# openbook.net
KiCad netlist of a schematic drawn in EAGLE
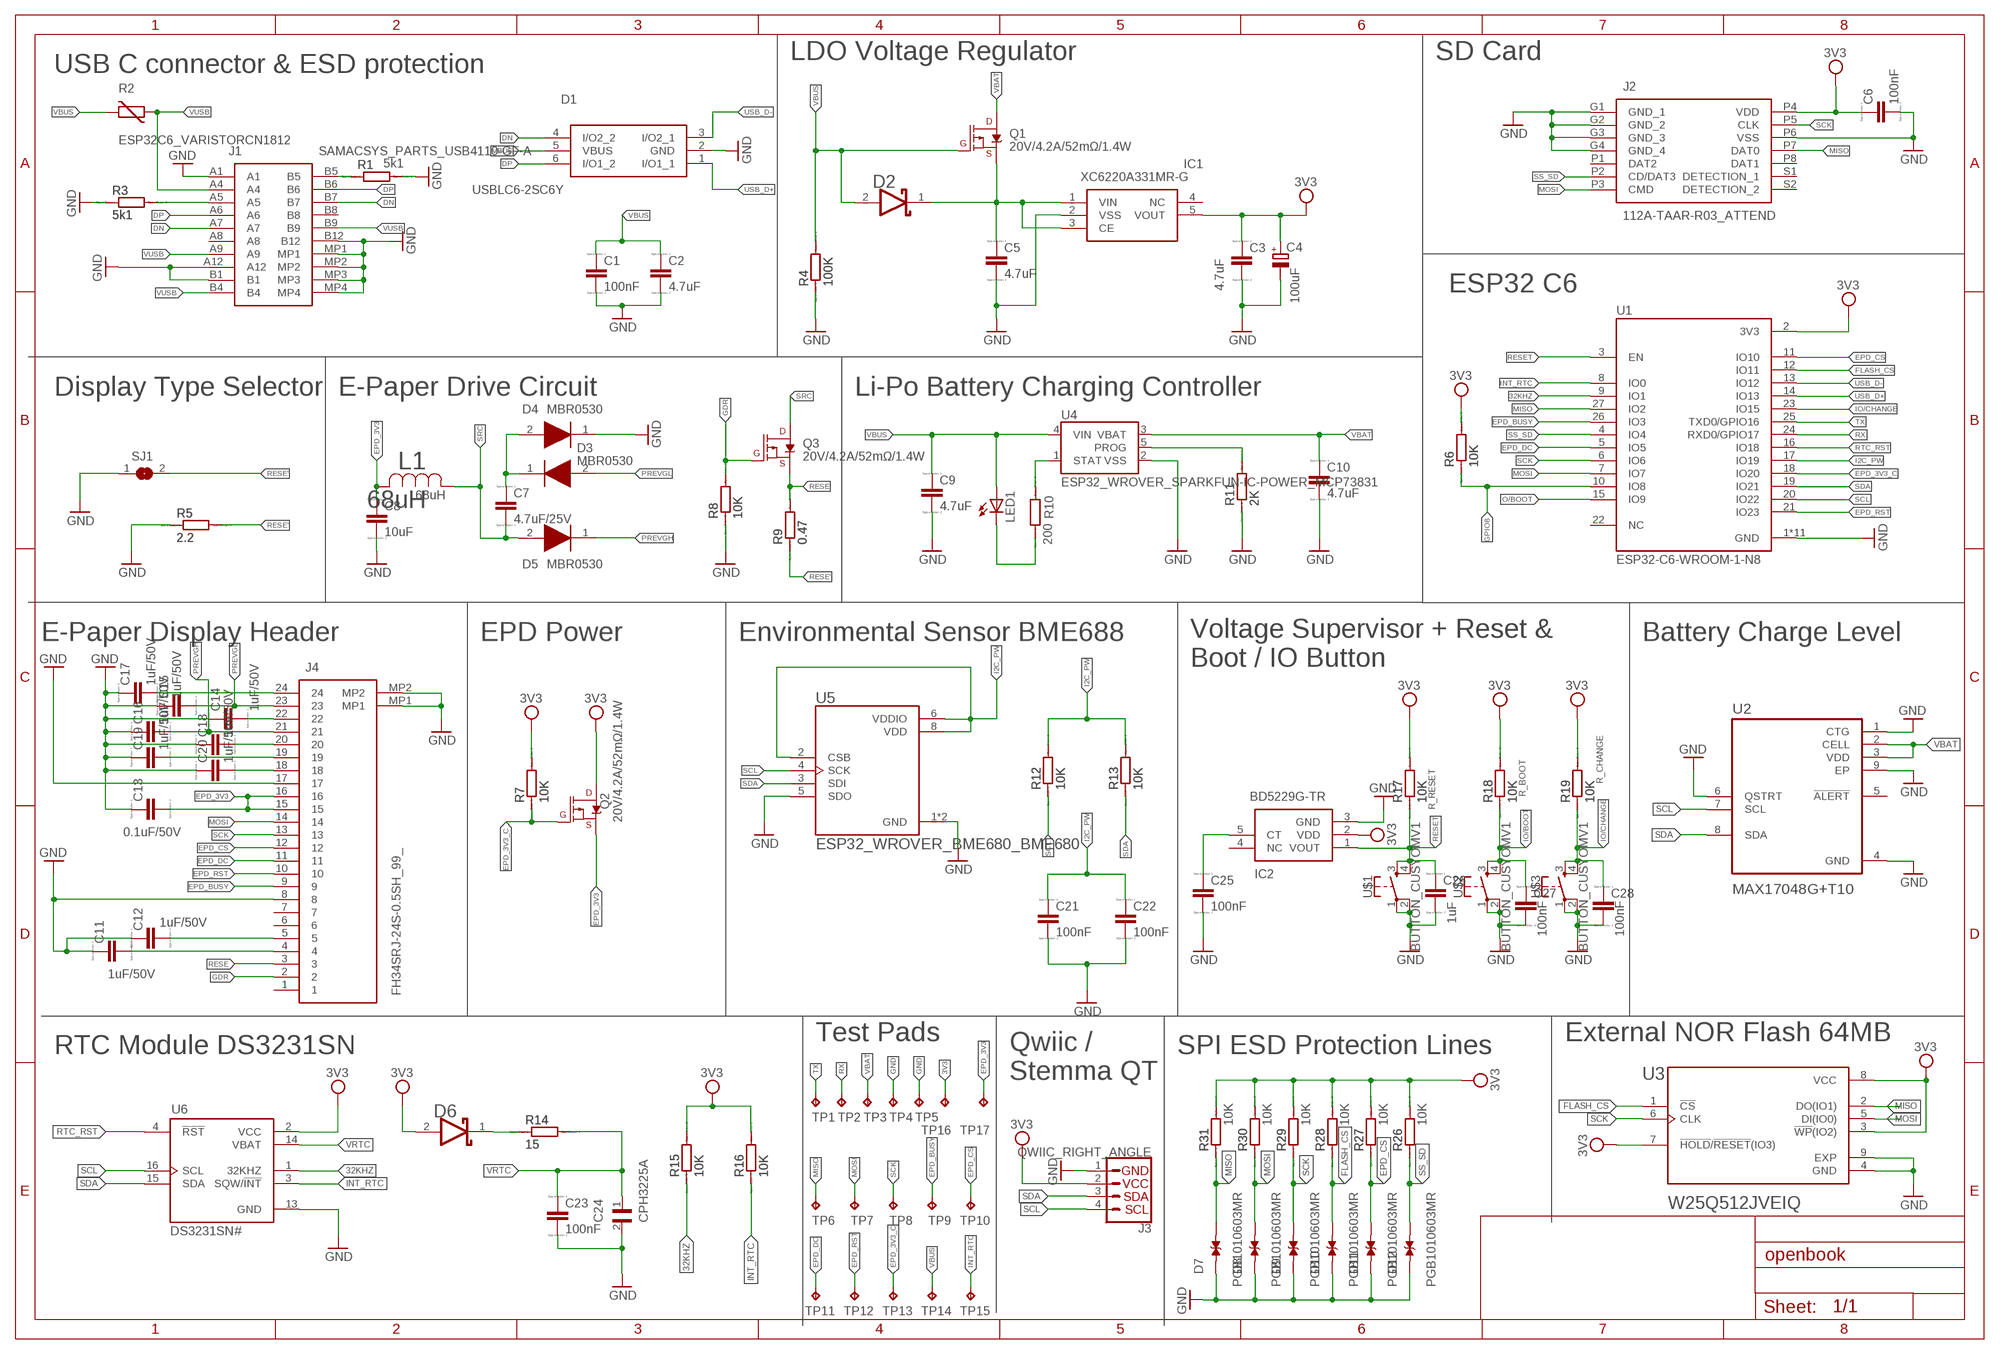
[diagram p0: schematic, sheet 1]

(export (version "E")
  (design (tool "Eeschema 10.0.6"))
  (components
    (comp (ref "C1")
      (value "100nF")
      (footprint "eagle-import:EAGLE-LTSPICE_C0402")
      (libsource (lib "eagle-import") (part "EAGLE-LTSPICE_CC0402"))
    )
    (comp (ref "C2")
      (value "4.7uF")
      (footprint "eagle-import:EAGLE-LTSPICE_C0402")
      (libsource (lib "eagle-import") (part "EAGLE-LTSPICE_CC0402"))
    )
    (comp (ref "C3")
      (value "4.7uF")
      (footprint "eagle-import:EAGLE-LTSPICE_C0402")
      (libsource (lib "eagle-import") (part "EAGLE-LTSPICE_CC0402"))
    )
    (comp (ref "C4")
      (value "100uF")
      (footprint "eagle-import:RCL_CT3528")
      (libsource (lib "eagle-import") (part "RCL_CPOL-EUCT3528"))
    )
    (comp (ref "C5")
      (value "4.7uF")
      (footprint "eagle-import:EAGLE-LTSPICE_C0402")
      (libsource (lib "eagle-import") (part "EAGLE-LTSPICE_CC0402"))
    )
    (comp (ref "C6")
      (value "100nF")
      (footprint "eagle-import:EAGLE-LTSPICE_C0402")
      (libsource (lib "eagle-import") (part "EAGLE-LTSPICE_CC0402"))
    )
    (comp (ref "C7")
      (value "4.7uF/25V")
      (footprint "eagle-import:EAGLE-LTSPICE_C0402")
      (libsource (lib "eagle-import") (part "EAGLE-LTSPICE_CC0402"))
    )
    (comp (ref "C8")
      (value "10uF")
      (footprint "eagle-import:EAGLE-LTSPICE_C0402")
      (libsource (lib "eagle-import") (part "EAGLE-LTSPICE_CC0402"))
    )
    (comp (ref "C9")
      (value "4.7uF")
      (footprint "eagle-import:EAGLE-LTSPICE_C0402")
      (libsource (lib "eagle-import") (part "EAGLE-LTSPICE_CC0402"))
    )
    (comp (ref "C10")
      (value "4.7uF")
      (footprint "eagle-import:EAGLE-LTSPICE_C0402")
      (libsource (lib "eagle-import") (part "EAGLE-LTSPICE_CC0402"))
    )
    (comp (ref "C11")
      (value "1uF/50V")
      (footprint "eagle-import:EAGLE-LTSPICE_C0402")
      (libsource (lib "eagle-import") (part "EAGLE-LTSPICE_CC0402"))
    )
    (comp (ref "C12")
      (value "1uF/50V")
      (footprint "eagle-import:EAGLE-LTSPICE_C0402")
      (libsource (lib "eagle-import") (part "EAGLE-LTSPICE_CC0402"))
    )
    (comp (ref "C13")
      (value "0.1uF/50V")
      (footprint "eagle-import:EAGLE-LTSPICE_C0402")
      (libsource (lib "eagle-import") (part "EAGLE-LTSPICE_CC0402"))
    )
    (comp (ref "C14")
      (value "1uF/50V")
      (footprint "eagle-import:EAGLE-LTSPICE_C0402")
      (libsource (lib "eagle-import") (part "EAGLE-LTSPICE_CC0402"))
    )
    (comp (ref "C15")
      (value "1uF/50V")
      (footprint "eagle-import:EAGLE-LTSPICE_C0402")
      (libsource (lib "eagle-import") (part "EAGLE-LTSPICE_CC0402"))
    )
    (comp (ref "C16")
      (value "1uF/50V")
      (footprint "eagle-import:EAGLE-LTSPICE_C0402")
      (libsource (lib "eagle-import") (part "EAGLE-LTSPICE_CC0402"))
    )
    (comp (ref "C17")
      (value "1uF/50V")
      (footprint "eagle-import:EAGLE-LTSPICE_C0402")
      (libsource (lib "eagle-import") (part "EAGLE-LTSPICE_CC0402"))
    )
    (comp (ref "C18")
      (value "1uF/50V")
      (footprint "eagle-import:EAGLE-LTSPICE_C0402")
      (libsource (lib "eagle-import") (part "EAGLE-LTSPICE_CC0402"))
    )
    (comp (ref "C19")
      (value "1uF/50V")
      (footprint "eagle-import:EAGLE-LTSPICE_C0402")
      (libsource (lib "eagle-import") (part "EAGLE-LTSPICE_CC0402"))
    )
    (comp (ref "C20")
      (value "1uF/50V")
      (footprint "eagle-import:EAGLE-LTSPICE_C0402")
      (libsource (lib "eagle-import") (part "EAGLE-LTSPICE_CC0402"))
    )
    (comp (ref "C21")
      (value "100nF")
      (footprint "eagle-import:EAGLE-LTSPICE_C0402")
      (libsource (lib "eagle-import") (part "EAGLE-LTSPICE_CC0402"))
    )
    (comp (ref "C22")
      (value "100nF")
      (footprint "eagle-import:EAGLE-LTSPICE_C0402")
      (libsource (lib "eagle-import") (part "EAGLE-LTSPICE_CC0402"))
    )
    (comp (ref "C23")
      (value "100nF")
      (footprint "eagle-import:EAGLE-LTSPICE_C0402")
      (libsource (lib "eagle-import") (part "EAGLE-LTSPICE_CC0402"))
    )
    (comp (ref "C24")
      (value "CPH3225A")
      (footprint "eagle-import:CAPCP3225X100N")
      (fields (field (name "MF") "Seiko Instruments"))
      (libsource (lib "eagle-import") (part "CPH3225A"))
    )
    (comp (ref "C25")
      (value "100nF")
      (footprint "eagle-import:EAGLE-LTSPICE_C0402")
      (libsource (lib "eagle-import") (part "EAGLE-LTSPICE_CC0402"))
    )
    (comp (ref "C26")
      (value "1uF")
      (footprint "eagle-import:EAGLE-LTSPICE_C0402")
      (libsource (lib "eagle-import") (part "EAGLE-LTSPICE_CC0402"))
    )
    (comp (ref "C27")
      (value "100nF")
      (footprint "eagle-import:EAGLE-LTSPICE_C0402")
      (libsource (lib "eagle-import") (part "EAGLE-LTSPICE_CC0402"))
    )
    (comp (ref "C28")
      (value "100nF")
      (footprint "eagle-import:EAGLE-LTSPICE_C0402")
      (libsource (lib "eagle-import") (part "EAGLE-LTSPICE_CC0402"))
    )
    (comp (ref "D1")
      (value "USBLC6-2SC6Y")
      (footprint "eagle-import:SOT95P280X145-6N")
      (fields (field (name "MF") "STMicroelectronics"))
      (libsource (lib "eagle-import") (part "USBLC6-2SC6Y"))
    )
    (comp (ref "D2")
      (value "ESP32_WROVER_AVX---SD0805S020S1R0_AVX_SD0805S020S1R0_0_0AVX_SD0805S020S1R0_0_0")
      (footprint "eagle-import:ESP32_WROVER_AVX---SD0805S020S1R0_AVX_SD0805S020S1R0_0")
      (fields
        (field (name "DIGIKEY_PART_NUMBER") "478-7800-1-ND")
        (field (name "MF") "AVX")
        (field (name "MOUSER_PART_NUMBER") "581-SD0805S020S1R0")
      )
      (libsource (lib "eagle-import") (part "ESP32_WROVER_AVX---SD0805S020S1R0_AVX_SD0805S020S1R0_0_0AVX_SD0805S020S1R0_0_0"))
    )
    (comp (ref "D3")
      (value "MBR0530")
      (footprint "eagle-import:SOD3716X135N")
      (fields (field (name "MF") "ON Semiconductor"))
      (libsource (lib "eagle-import") (part "MBR0530"))
    )
    (comp (ref "D4")
      (value "MBR0530")
      (footprint "eagle-import:SOD3716X135N")
      (fields (field (name "MF") "ON Semiconductor"))
      (libsource (lib "eagle-import") (part "MBR0530"))
    )
    (comp (ref "D5")
      (value "MBR0530")
      (footprint "eagle-import:SOD3716X135N")
      (fields (field (name "MF") "ON Semiconductor"))
      (libsource (lib "eagle-import") (part "MBR0530"))
    )
    (comp (ref "D6")
      (value "ESP32_WROVER_AVX---SD0805S020S1R0_AVX_SD0805S020S1R0_0_0AVX_SD0805S020S1R0_0_0")
      (footprint "eagle-import:ESP32_WROVER_AVX---SD0805S020S1R0_AVX_SD0805S020S1R0_0")
      (fields
        (field (name "DIGIKEY_PART_NUMBER") "478-7800-1-ND")
        (field (name "MF") "AVX")
        (field (name "MOUSER_PART_NUMBER") "581-SD0805S020S1R0")
      )
      (libsource (lib "eagle-import") (part "ESP32_WROVER_AVX---SD0805S020S1R0_AVX_SD0805S020S1R0_0_0AVX_SD0805S020S1R0_0_0"))
    )
    (comp (ref "D7")
      (value "PGB1010603MR")
      (footprint "eagle-import:DIOC1608X36N")
      (fields (field (name "MF") "Littelfuse Inc."))
      (libsource (lib "eagle-import") (part "PGB1010603MR"))
    )
    (comp (ref "D8")
      (value "PGB1010603MR")
      (footprint "eagle-import:DIOC1608X36N")
      (fields (field (name "MF") "Littelfuse Inc."))
      (libsource (lib "eagle-import") (part "PGB1010603MR"))
    )
    (comp (ref "D9")
      (value "PGB1010603MR")
      (footprint "eagle-import:DIOC1608X36N")
      (fields (field (name "MF") "Littelfuse Inc."))
      (libsource (lib "eagle-import") (part "PGB1010603MR"))
    )
    (comp (ref "D10")
      (value "PGB1010603MR")
      (footprint "eagle-import:DIOC1608X36N")
      (fields (field (name "MF") "Littelfuse Inc."))
      (libsource (lib "eagle-import") (part "PGB1010603MR"))
    )
    (comp (ref "D11")
      (value "PGB1010603MR")
      (footprint "eagle-import:DIOC1608X36N")
      (fields (field (name "MF") "Littelfuse Inc."))
      (libsource (lib "eagle-import") (part "PGB1010603MR"))
    )
    (comp (ref "D12")
      (value "PGB1010603MR")
      (footprint "eagle-import:DIOC1608X36N")
      (fields (field (name "MF") "Littelfuse Inc."))
      (libsource (lib "eagle-import") (part "PGB1010603MR"))
    )
    (comp (ref "IC1")
      (value "XC6220A331MR-G")
      (footprint "eagle-import:SOT95P280X120-5N")
      (fields (field (name "MOUSER_PART_NUMBER") "865-XC6220A331MR-G"))
      (libsource (lib "eagle-import") (part "XC6220A331MR-G"))
    )
    (comp (ref "IC2")
      (value "BD5229G-TR")
      (footprint "eagle-import:SOT95P280X125-5N")
      (fields (field (name "MOUSER_PART_NUMBER") "755-BD5229G-TR"))
      (libsource (lib "eagle-import") (part "BD5229G-TR"))
    )
    (comp (ref "J1")
      (value "SAMACSYS_PARTS_USB4110-GF-A")
      (footprint "eagle-import:SAMACSYS_PARTS_USB4110GFA")
      (fields
        (field (name "MANUFACTURER_PART_NUMBER") "USB4110-GF-A")
        (field (name "MOUSER_PART_NUMBER") "640-USB4110-GF-A")
      )
      (libsource (lib "eagle-import") (part "SAMACSYS_PARTS_USB4110-GF-A"))
    )
    (comp (ref "J2")
      (value "112A-TAAR-R03_ATTEND")
      (footprint "eagle-import:112ATAARR03ATTEND")
      (fields (field (name "MANUFACTURER_PART_NUMBER") "112A-TAAR-R03 ATTEND"))
      (libsource (lib "eagle-import") (part "112A-TAAR-R03_ATTEND"))
    )
    (comp (ref "J3")
      (value "QWIIC_RIGHT_ANGLE")
      (footprint "eagle-import:JST04_1MM_RA")
      (libsource (lib "eagle-import") (part "QWIIC_CONNECTORJS-1MM"))
    )
    (comp (ref "J4")
      (value "FH34SRJ-24S-0.5SH_99_")
      (footprint "eagle-import:FH34SRJ24S05SH99")
      (fields
        (field (name "MANUFACTURER_PART_NUMBER") "FH34SRJ-24S-0.5SH(99)")
        (field (name "MOUSER_PART_NUMBER") "798-FH34SRJ24S05SH99")
      )
      (libsource (lib "eagle-import") (part "FH34SRJ-24S-0.5SH_99_"))
    )
    (comp (ref "L1")
      (value "68uH")
      (footprint "eagle-import:IND_4828-WE-TPC_WRE")
      (fields
        (field (name "MANUFACTURER_PART_NUMBER") "744043680")
        (field (name "COPYRIGHT") "Copyright (C) 2024 Ultra Librarian. All rights reserved.")
      )
      (libsource (lib "eagle-import") (part "744043680IND_4828-WE-TPC_WRE"))
    )
    (comp (ref "LED1")
      (value "ADAFRUIT_LEDCHIP-LED0603")
      (footprint "eagle-import:ADAFRUIT_CHIP-LED0603")
      (libsource (lib "eagle-import") (part "ADAFRUIT_LEDCHIP-LED0603"))
    )
    (comp (ref "Q1")
      (value "20V/4.2A/52mΩ/1.4W")
      (footprint "eagle-import:ESP32_WROVER_SPARKFUN-DISCRETESEMI_SOT23-3")
      (libsource (lib "eagle-import") (part "ESP32_WROVER_SPARKFUN-DISCRETESEMI_MOSFET_PCH-DMG2305UX-7"))
    )
    (comp (ref "Q2")
      (value "20V/4.2A/52mΩ/1.4W")
      (footprint "eagle-import:ESP32_WROVER_SPARKFUN-DISCRETESEMI_SOT23-3")
      (libsource (lib "eagle-import") (part "ESP32_WROVER_SPARKFUN-DISCRETESEMI_MOSFET_PCH-DMG2305UX-7"))
    )
    (comp (ref "Q3")
      (value "20V/4.2A/52mΩ/1.4W")
      (footprint "eagle-import:ESP32_WROVER_SPARKFUN-DISCRETESEMI_SOT23-3")
      (libsource (lib "eagle-import") (part "ESP32_WROVER_SPARKFUN-DISCRETESEMI_MOSFET_PCH-DMG2305UX-7"))
    )
    (comp (ref "R1")
      (value "5k1")
      (footprint "eagle-import:ESP32_WROVER_EAGLE-LTSPICE_R0402")
      (libsource (lib "eagle-import") (part "ESP32_WROVER_EAGLE-LTSPICE_RR0402"))
    )
    (comp (ref "R2")
      (value "ESP32C6_VARISTORCN1812")
      (footprint "eagle-import:ESP32C6_VARISTOR_CT_CN1812")
      (libsource (lib "eagle-import") (part "ESP32C6_VARISTORCN1812"))
    )
    (comp (ref "R3")
      (value "5k1")
      (footprint "eagle-import:ESP32_WROVER_EAGLE-LTSPICE_R0402")
      (libsource (lib "eagle-import") (part "ESP32_WROVER_EAGLE-LTSPICE_RR0402"))
    )
    (comp (ref "R4")
      (value "100K")
      (footprint "eagle-import:ESP32_WROVER_EAGLE-LTSPICE_R0402")
      (libsource (lib "eagle-import") (part "ESP32_WROVER_EAGLE-LTSPICE_RR0402"))
    )
    (comp (ref "R5")
      (value "2.2")
      (footprint "eagle-import:ESP32_WROVER_EAGLE-LTSPICE_R0402")
      (libsource (lib "eagle-import") (part "ESP32_WROVER_EAGLE-LTSPICE_RR0402"))
    )
    (comp (ref "R6")
      (value "10K")
      (footprint "eagle-import:ESP32_WROVER_EAGLE-LTSPICE_R0402")
      (libsource (lib "eagle-import") (part "ESP32_WROVER_EAGLE-LTSPICE_RR0402"))
    )
    (comp (ref "R7")
      (value "10K")
      (footprint "eagle-import:ESP32_WROVER_EAGLE-LTSPICE_R0402")
      (libsource (lib "eagle-import") (part "ESP32_WROVER_EAGLE-LTSPICE_RR0402"))
    )
    (comp (ref "R8")
      (value "10K")
      (footprint "eagle-import:ESP32_WROVER_EAGLE-LTSPICE_R0402")
      (libsource (lib "eagle-import") (part "ESP32_WROVER_EAGLE-LTSPICE_RR0402"))
    )
    (comp (ref "R9")
      (value "0.47")
      (footprint "eagle-import:ESP32_WROVER_EAGLE-LTSPICE_R0402")
      (libsource (lib "eagle-import") (part "ESP32_WROVER_EAGLE-LTSPICE_RR0402"))
    )
    (comp (ref "R10")
      (value "200")
      (footprint "eagle-import:ESP32_WROVER_EAGLE-LTSPICE_R0402")
      (libsource (lib "eagle-import") (part "ESP32_WROVER_EAGLE-LTSPICE_RR0402"))
    )
    (comp (ref "R11")
      (value "2K")
      (footprint "eagle-import:ESP32_WROVER_EAGLE-LTSPICE_R0402")
      (libsource (lib "eagle-import") (part "ESP32_WROVER_EAGLE-LTSPICE_RR0402"))
    )
    (comp (ref "R12")
      (value "10K")
      (footprint "eagle-import:ESP32_WROVER_EAGLE-LTSPICE_R0402")
      (libsource (lib "eagle-import") (part "ESP32_WROVER_EAGLE-LTSPICE_RR0402"))
    )
    (comp (ref "R13")
      (value "10K")
      (footprint "eagle-import:ESP32_WROVER_EAGLE-LTSPICE_R0402")
      (libsource (lib "eagle-import") (part "ESP32_WROVER_EAGLE-LTSPICE_RR0402"))
    )
    (comp (ref "R14")
      (value "15")
      (footprint "eagle-import:ESP32_WROVER_EAGLE-LTSPICE_R0402")
      (libsource (lib "eagle-import") (part "ESP32_WROVER_EAGLE-LTSPICE_RR0402"))
    )
    (comp (ref "R15")
      (value "10K")
      (footprint "eagle-import:ESP32_WROVER_EAGLE-LTSPICE_R0402")
      (libsource (lib "eagle-import") (part "ESP32_WROVER_EAGLE-LTSPICE_RR0402"))
    )
    (comp (ref "R16")
      (value "10K")
      (footprint "eagle-import:ESP32_WROVER_EAGLE-LTSPICE_R0402")
      (libsource (lib "eagle-import") (part "ESP32_WROVER_EAGLE-LTSPICE_RR0402"))
    )
    (comp (ref "R17")
      (value "10K")
      (footprint "eagle-import:ESP32_WROVER_EAGLE-LTSPICE_R0402")
      (libsource (lib "eagle-import") (part "ESP32_WROVER_EAGLE-LTSPICE_RR0402"))
    )
    (comp (ref "R18")
      (value "10K")
      (footprint "eagle-import:ESP32_WROVER_EAGLE-LTSPICE_R0402")
      (libsource (lib "eagle-import") (part "ESP32_WROVER_EAGLE-LTSPICE_RR0402"))
    )
    (comp (ref "R19")
      (value "10K")
      (footprint "eagle-import:ESP32_WROVER_EAGLE-LTSPICE_R0402")
      (libsource (lib "eagle-import") (part "ESP32_WROVER_EAGLE-LTSPICE_RR0402"))
    )
    (comp (ref "R26")
      (value "10K")
      (footprint "eagle-import:ESP32_WROVER_EAGLE-LTSPICE_R0402")
      (libsource (lib "eagle-import") (part "ESP32_WROVER_EAGLE-LTSPICE_RR0402"))
    )
    (comp (ref "R27")
      (value "10K")
      (footprint "eagle-import:ESP32_WROVER_EAGLE-LTSPICE_R0402")
      (libsource (lib "eagle-import") (part "ESP32_WROVER_EAGLE-LTSPICE_RR0402"))
    )
    (comp (ref "R28")
      (value "10K")
      (footprint "eagle-import:ESP32_WROVER_EAGLE-LTSPICE_R0402")
      (libsource (lib "eagle-import") (part "ESP32_WROVER_EAGLE-LTSPICE_RR0402"))
    )
    (comp (ref "R29")
      (value "10K")
      (footprint "eagle-import:ESP32_WROVER_EAGLE-LTSPICE_R0402")
      (libsource (lib "eagle-import") (part "ESP32_WROVER_EAGLE-LTSPICE_RR0402"))
    )
    (comp (ref "R30")
      (value "10K")
      (footprint "eagle-import:ESP32_WROVER_EAGLE-LTSPICE_R0402")
      (libsource (lib "eagle-import") (part "ESP32_WROVER_EAGLE-LTSPICE_RR0402"))
    )
    (comp (ref "R31")
      (value "10K")
      (footprint "eagle-import:ESP32_WROVER_EAGLE-LTSPICE_R0402")
      (libsource (lib "eagle-import") (part "ESP32_WROVER_EAGLE-LTSPICE_RR0402"))
    )
    (comp (ref "SJ1") (value "SJ") (footprint "eagle-import:SJ") (libsource (lib "eagle-import") (part "SJ")))
    (comp (ref "TP1")
      (value "TPTP20R")
      (footprint "eagle-import:TP20R")
      (libsource (lib "eagle-import") (part "TPTP20R"))
    )
    (comp (ref "TP2")
      (value "TPTP20R")
      (footprint "eagle-import:TP20R")
      (libsource (lib "eagle-import") (part "TPTP20R"))
    )
    (comp (ref "TP3")
      (value "TPTP20R")
      (footprint "eagle-import:TP20R")
      (libsource (lib "eagle-import") (part "TPTP20R"))
    )
    (comp (ref "TP4")
      (value "TPTP20R")
      (footprint "eagle-import:TP20R")
      (libsource (lib "eagle-import") (part "TPTP20R"))
    )
    (comp (ref "TP5")
      (value "TPTP20R")
      (footprint "eagle-import:TP20R")
      (libsource (lib "eagle-import") (part "TPTP20R"))
    )
    (comp (ref "TP6")
      (value "TPTP20R")
      (footprint "eagle-import:TP20R")
      (libsource (lib "eagle-import") (part "TPTP20R"))
    )
    (comp (ref "TP7")
      (value "TPTP20R")
      (footprint "eagle-import:TP20R")
      (libsource (lib "eagle-import") (part "TPTP20R"))
    )
    (comp (ref "TP8")
      (value "TPTP20R")
      (footprint "eagle-import:TP20R")
      (libsource (lib "eagle-import") (part "TPTP20R"))
    )
    (comp (ref "TP9")
      (value "TPTP20R")
      (footprint "eagle-import:TP20R")
      (libsource (lib "eagle-import") (part "TPTP20R"))
    )
    (comp (ref "TP10")
      (value "TPTP20R")
      (footprint "eagle-import:TP20R")
      (libsource (lib "eagle-import") (part "TPTP20R"))
    )
    (comp (ref "TP11")
      (value "TPTP20R")
      (footprint "eagle-import:TP20R")
      (libsource (lib "eagle-import") (part "TPTP20R"))
    )
    (comp (ref "TP12")
      (value "TPTP20R")
      (footprint "eagle-import:TP20R")
      (libsource (lib "eagle-import") (part "TPTP20R"))
    )
    (comp (ref "TP13")
      (value "TPTP20R")
      (footprint "eagle-import:TP20R")
      (libsource (lib "eagle-import") (part "TPTP20R"))
    )
    (comp (ref "TP14")
      (value "TPTP20R")
      (footprint "eagle-import:TP20R")
      (libsource (lib "eagle-import") (part "TPTP20R"))
    )
    (comp (ref "TP15")
      (value "TPTP20R")
      (footprint "eagle-import:TP20R")
      (libsource (lib "eagle-import") (part "TPTP20R"))
    )
    (comp (ref "TP16")
      (value "TPTP20R")
      (footprint "eagle-import:TP20R")
      (libsource (lib "eagle-import") (part "TPTP20R"))
    )
    (comp (ref "TP17")
      (value "TPTP20R")
      (footprint "eagle-import:TP20R")
      (libsource (lib "eagle-import") (part "TPTP20R"))
    )
    (comp (ref "U$1")
      (value "BUTTON_CUSYOMV1")
      (footprint "eagle-import:MYBUTTON")
      (libsource (lib "eagle-import") (part "BUTTON_CUSYOMV1"))
    )
    (comp (ref "U$2")
      (value "BUTTON_CUSYOMV1")
      (footprint "eagle-import:MYBUTTON")
      (libsource (lib "eagle-import") (part "BUTTON_CUSYOMV1"))
    )
    (comp (ref "U$3")
      (value "BUTTON_CUSYOMV1")
      (footprint "eagle-import:MYBUTTON")
      (libsource (lib "eagle-import") (part "BUTTON_CUSYOMV1"))
    )
    (comp (ref "U1")
      (value "ESP32-C6-WROOM-1-N8")
      (footprint "eagle-import:XCVR_ESP32-C6-WROOM-1-N8")
      (fields (field (name "MF") "Espressif Systems"))
      (libsource (lib "eagle-import") (part "ESP32-C6-WROOM-1-N8"))
    )
    (comp (ref "U2")
      (value "MAX17048G+T10")
      (footprint "eagle-import:SON50P200X200X80-9N")
      (fields (field (name "MF") "Analog Devices"))
      (libsource (lib "eagle-import") (part "MAX17048G+T10"))
    )
    (comp (ref "U3")
      (value "W25Q512JVEIQ")
      (footprint "eagle-import:SON127P600X800X80-9N")
      (fields (field (name "MF") "Winbond Electronics"))
      (libsource (lib "eagle-import") (part "W25Q512JVEIQ"))
    )
    (comp (ref "U4")
      (value "ESP32_WROVER_SPARKFUN-IC-POWER_MCP73831")
      (footprint "eagle-import:ESP32_WROVER_SPARKFUN-IC-POWER_SOT23-5")
      (libsource (lib "eagle-import") (part "ESP32_WROVER_SPARKFUN-IC-POWER_MCP73831"))
    )
    (comp (ref "U5")
      (value "ESP32_WROVER_BME680_BME680")
      (footprint "eagle-import:ESP32_WROVER_BME680_PSON80P300X300X100-8N")
      (fields (field (name "MF") "Bosch Sensortec") (field (name "MP") "BME680"))
      (libsource (lib "eagle-import") (part "ESP32_WROVER_BME680_BME680"))
    )
    (comp (ref "U6")
      (value "DS3231SN#")
      (footprint "eagle-import:SOIC127P1032X265-16N")
      (fields (field (name "MF") "Analog Devices"))
      (libsource (lib "eagle-import") (part "DS3231SN#"))
    )
  )
  (nets
    (net (code "1") (name "3V3") (class "Default")
      (node (ref "C3") (pin "1") (pinfunction "1_1") (pintype "passive"))
      (node (ref "C4") (pin "+") (pinfunction "+_+") (pintype "passive"))
      (node (ref "C6") (pin "1") (pinfunction "1_1") (pintype "passive"))
      (node (ref "D6") (pin "2") (pinfunction "ANODE_2") (pintype "bidirectional"))
      (node (ref "IC1") (pin "5") (pinfunction "VOUT_5") (pintype "bidirectional"))
      (node (ref "IC2") (pin "2") (pinfunction "VDD_2") (pintype "bidirectional"))
      (node (ref "J2") (pin "P4") (pinfunction "VDD_P4") (pintype "bidirectional"))
      (node (ref "J3") (pin "2") (pinfunction "2_2") (pintype "power_in"))
      (node (ref "Q2") (pin "3") (pinfunction "D_3") (pintype "bidirectional"))
      (node (ref "R15") (pin "2") (pinfunction "2_2") (pintype "passive"))
      (node (ref "R16") (pin "2") (pinfunction "2_2") (pintype "passive"))
      (node (ref "R17") (pin "2") (pinfunction "2_2") (pintype "passive"))
      (node (ref "R18") (pin "2") (pinfunction "2_2") (pintype "passive"))
      (node (ref "R19") (pin "2") (pinfunction "2_2") (pintype "passive"))
      (node (ref "R26") (pin "2") (pinfunction "2_2") (pintype "passive"))
      (node (ref "R27") (pin "2") (pinfunction "2_2") (pintype "passive"))
      (node (ref "R28") (pin "2") (pinfunction "2_2") (pintype "passive"))
      (node (ref "R29") (pin "2") (pinfunction "2_2") (pintype "passive"))
      (node (ref "R30") (pin "2") (pinfunction "2_2") (pintype "passive"))
      (node (ref "R31") (pin "2") (pinfunction "2_2") (pintype "passive"))
      (node (ref "R6") (pin "2") (pinfunction "2_2") (pintype "passive"))
      (node (ref "R7") (pin "2") (pinfunction "2_2") (pintype "passive"))
      (node (ref "TP16") (pin "TP") (pinfunction "TP_TP") (pintype "input"))
      (node (ref "U1") (pin "2") (pinfunction "3V3_2") (pintype "power_in"))
      (node (ref "U3") (pin "3") (pinfunction "~{WP}(IO2)_3") (pintype "bidirectional"))
      (node (ref "U3") (pin "7") (pinfunction "~{HOLD}/~{RESET}(IO3)_7") (pintype "bidirectional"))
      (node (ref "U3") (pin "8") (pinfunction "VCC_8") (pintype "power_in"))
      (node (ref "U6") (pin "2") (pinfunction "VCC_2") (pintype "power_in"))
    )
    (net (code "2") (name "32KHZ") (class "Default")
      (node (ref "R15") (pin "1") (pinfunction "1_1") (pintype "passive"))
      (node (ref "U1") (pin "9") (pinfunction "IO1_9") (pintype "bidirectional"))
      (node (ref "U6") (pin "1") (pinfunction "32KHZ_1") (pintype "output"))
    )
    (net (code "3") (name "DN") (class "Default")
      (node (ref "D1") (pin "4") (pinfunction "I/O2_2_4") (pintype "bidirectional"))
      (node (ref "J1") (pin "A7") (pinfunction "A7_A7") (pintype "bidirectional"))
      (node (ref "J1") (pin "B7") (pinfunction "B7_B7") (pintype "bidirectional"))
    )
    (net (code "4") (name "DP") (class "Default")
      (node (ref "D1") (pin "6") (pinfunction "I/O1_2_6") (pintype "bidirectional"))
      (node (ref "J1") (pin "A6") (pinfunction "A6_A6") (pintype "bidirectional"))
      (node (ref "J1") (pin "B6") (pinfunction "B6_B6") (pintype "bidirectional"))
    )
    (net (code "5") (name "EPD_3V3") (class "Default")
      (node (ref "C13") (pin "2") (pinfunction "2_2") (pintype "passive"))
      (node (ref "C8") (pin "1") (pinfunction "1_1") (pintype "passive"))
      (node (ref "J4") (pin "15") (pinfunction "15_15") (pintype "bidirectional"))
      (node (ref "J4") (pin "16") (pinfunction "16_16") (pintype "bidirectional"))
      (node (ref "L1") (pin "2") (pinfunction "2_2") (pintype "passive"))
      (node (ref "Q2") (pin "2") (pinfunction "S_2") (pintype "bidirectional"))
      (node (ref "TP17") (pin "TP") (pinfunction "TP_TP") (pintype "input"))
    )
    (net (code "6") (name "EPD_3V3_C") (class "Default")
      (node (ref "Q2") (pin "1") (pinfunction "G_1") (pintype "bidirectional"))
      (node (ref "R7") (pin "1") (pinfunction "1_1") (pintype "passive"))
      (node (ref "TP13") (pin "TP") (pinfunction "TP_TP") (pintype "input"))
      (node (ref "U1") (pin "18") (pinfunction "IO20_18") (pintype "bidirectional"))
    )
    (net (code "7") (name "EPD_BUSY") (class "Default")
      (node (ref "J4") (pin "9") (pinfunction "9_9") (pintype "bidirectional"))
      (node (ref "TP9") (pin "TP") (pinfunction "TP_TP") (pintype "input"))
      (node (ref "U1") (pin "26") (pinfunction "IO3_26") (pintype "bidirectional"))
    )
    (net (code "8") (name "EPD_CS") (class "Default")
      (node (ref "D11") (pin "2") (pinfunction "2_2") (pintype "passive"))
      (node (ref "J4") (pin "12") (pinfunction "12_12") (pintype "bidirectional"))
      (node (ref "R27") (pin "1") (pinfunction "1_1") (pintype "passive"))
      (node (ref "TP10") (pin "TP") (pinfunction "TP_TP") (pintype "input"))
      (node (ref "U1") (pin "11") (pinfunction "IO10_11") (pintype "bidirectional"))
    )
    (net (code "9") (name "EPD_DC") (class "Default")
      (node (ref "J4") (pin "11") (pinfunction "11_11") (pintype "bidirectional"))
      (node (ref "TP11") (pin "TP") (pinfunction "TP_TP") (pintype "input"))
      (node (ref "U1") (pin "5") (pinfunction "IO5_5") (pintype "bidirectional"))
    )
    (net (code "10") (name "EPD_RST") (class "Default")
      (node (ref "J4") (pin "10") (pinfunction "10_10") (pintype "bidirectional"))
      (node (ref "TP12") (pin "TP") (pinfunction "TP_TP") (pintype "input"))
      (node (ref "U1") (pin "21") (pinfunction "IO23_21") (pintype "bidirectional"))
    )
    (net (code "11") (name "FLASH_CS") (class "Default")
      (node (ref "D10") (pin "2") (pinfunction "2_2") (pintype "passive"))
      (node (ref "R28") (pin "1") (pinfunction "1_1") (pintype "passive"))
      (node (ref "U1") (pin "12") (pinfunction "IO11_12") (pintype "bidirectional"))
      (node (ref "U3") (pin "1") (pinfunction "~{CS}_1") (pintype "input"))
    )
    (net (code "12") (name "GDR") (class "Default")
      (node (ref "J4") (pin "2") (pinfunction "2_2") (pintype "bidirectional"))
      (node (ref "Q3") (pin "1") (pinfunction "G_1") (pintype "bidirectional"))
      (node (ref "R8") (pin "2") (pinfunction "2_2") (pintype "passive"))
    )
    (net (code "13") (name "GND") (class "Default")
      (node (ref "C1") (pin "2") (pinfunction "2_2") (pintype "passive"))
      (node (ref "C10") (pin "2") (pinfunction "2_2") (pintype "passive"))
      (node (ref "C11") (pin "1") (pinfunction "1_1") (pintype "passive"))
      (node (ref "C12") (pin "1") (pinfunction "1_1") (pintype "passive"))
      (node (ref "C13") (pin "1") (pinfunction "1_1") (pintype "passive"))
      (node (ref "C14") (pin "1") (pinfunction "1_1") (pintype "passive"))
      (node (ref "C15") (pin "1") (pinfunction "1_1") (pintype "passive"))
      (node (ref "C16") (pin "1") (pinfunction "1_1") (pintype "passive"))
      (node (ref "C17") (pin "1") (pinfunction "1_1") (pintype "passive"))
      (node (ref "C18") (pin "1") (pinfunction "1_1") (pintype "passive"))
      (node (ref "C19") (pin "1") (pinfunction "1_1") (pintype "passive"))
      (node (ref "C2") (pin "2") (pinfunction "2_2") (pintype "passive"))
      (node (ref "C20") (pin "1") (pinfunction "1_1") (pintype "passive"))
      (node (ref "C21") (pin "2") (pinfunction "2_2") (pintype "passive"))
      (node (ref "C22") (pin "2") (pinfunction "2_2") (pintype "passive"))
      (node (ref "C23") (pin "2") (pinfunction "2_2") (pintype "passive"))
      (node (ref "C24") (pin "2") (pinfunction "2_2") (pintype "passive"))
      (node (ref "C25") (pin "2") (pinfunction "2_2") (pintype "passive"))
      (node (ref "C26") (pin "2") (pinfunction "2_2") (pintype "passive"))
      (node (ref "C27") (pin "2") (pinfunction "2_2") (pintype "passive"))
      (node (ref "C28") (pin "2") (pinfunction "2_2") (pintype "passive"))
      (node (ref "C3") (pin "2") (pinfunction "2_2") (pintype "passive"))
      (node (ref "C4") (pin "-") (pinfunction "-_-") (pintype "passive"))
      (node (ref "C5") (pin "2") (pinfunction "2_2") (pintype "passive"))
      (node (ref "C6") (pin "2") (pinfunction "2_2") (pintype "passive"))
      (node (ref "C8") (pin "2") (pinfunction "2_2") (pintype "passive"))
      (node (ref "C9") (pin "2") (pinfunction "2_2") (pintype "passive"))
      (node (ref "D1") (pin "2") (pinfunction "GND_2") (pintype "bidirectional"))
      (node (ref "D10") (pin "1") (pinfunction "1_1") (pintype "passive"))
      (node (ref "D11") (pin "1") (pinfunction "1_1") (pintype "passive"))
      (node (ref "D12") (pin "1") (pinfunction "1_1") (pintype "passive"))
      (node (ref "D4") (pin "1") (pinfunction "K_1") (pintype "bidirectional"))
      (node (ref "D7") (pin "1") (pinfunction "1_1") (pintype "passive"))
      (node (ref "D8") (pin "1") (pinfunction "1_1") (pintype "passive"))
      (node (ref "D9") (pin "1") (pinfunction "1_1") (pintype "passive"))
      (node (ref "IC1") (pin "2") (pinfunction "VSS_2") (pintype "bidirectional"))
      (node (ref "IC2") (pin "3") (pinfunction "GND_3") (pintype "bidirectional"))
      (node (ref "J1") (pin "A1") (pinfunction "A1_A1") (pintype "bidirectional"))
      (node (ref "J1") (pin "A12") (pinfunction "A12_A12") (pintype "bidirectional"))
      (node (ref "J1") (pin "B1") (pinfunction "B1_B1") (pintype "bidirectional"))
      (node (ref "J1") (pin "B12") (pinfunction "B12_B12") (pintype "bidirectional"))
      (node (ref "J1") (pin "MP1") (pinfunction "MP1_MP1") (pintype "bidirectional"))
      (node (ref "J1") (pin "MP2") (pinfunction "MP2_MP2") (pintype "bidirectional"))
      (node (ref "J1") (pin "MP3") (pinfunction "MP3_MP3") (pintype "bidirectional"))
      (node (ref "J1") (pin "MP4") (pinfunction "MP4_MP4") (pintype "bidirectional"))
      (node (ref "J2") (pin "G1") (pinfunction "GND_1_G1") (pintype "bidirectional"))
      (node (ref "J2") (pin "G2") (pinfunction "GND_2_G2") (pintype "bidirectional"))
      (node (ref "J2") (pin "G3") (pinfunction "GND_3_G3") (pintype "bidirectional"))
      (node (ref "J2") (pin "G4") (pinfunction "GND_4_G4") (pintype "bidirectional"))
      (node (ref "J2") (pin "P6") (pinfunction "VSS_P6") (pintype "bidirectional"))
      (node (ref "J3") (pin "1") (pinfunction "1_1") (pintype "power_in"))
      (node (ref "J4") (pin "17") (pinfunction "17_17") (pintype "bidirectional"))
      (node (ref "J4") (pin "8") (pinfunction "8_8") (pintype "bidirectional"))
      (node (ref "J4") (pin "MP1") (pinfunction "MP1_MP1") (pintype "bidirectional"))
      (node (ref "J4") (pin "MP2") (pinfunction "MP2_MP2") (pintype "bidirectional"))
      (node (ref "R1") (pin "2") (pinfunction "2_2") (pintype "passive"))
      (node (ref "R11") (pin "1") (pinfunction "1_1") (pintype "passive"))
      (node (ref "R3") (pin "1") (pinfunction "1_1") (pintype "passive"))
      (node (ref "R4") (pin "1") (pinfunction "1_1") (pintype "passive"))
      (node (ref "R5") (pin "1") (pinfunction "1_1") (pintype "passive"))
      (node (ref "R8") (pin "1") (pinfunction "1_1") (pintype "passive"))
      (node (ref "SJ1") (pin "1") (pinfunction "1_1") (pintype "passive"))
      (node (ref "TP4") (pin "TP") (pinfunction "TP_TP") (pintype "input"))
      (node (ref "TP5") (pin "TP") (pinfunction "TP_TP") (pintype "input"))
      (node (ref "U$1") (pin "1") (pinfunction "1_1") (pintype "passive"))
      (node (ref "U$1") (pin "2") (pinfunction "2_2") (pintype "passive"))
      (node (ref "U$2") (pin "1") (pinfunction "1_1") (pintype "passive"))
      (node (ref "U$2") (pin "2") (pinfunction "2_2") (pintype "passive"))
      (node (ref "U$3") (pin "1") (pinfunction "1_1") (pintype "passive"))
      (node (ref "U$3") (pin "2") (pinfunction "2_2") (pintype "passive"))
      (node (ref "U1") (pin "1") (pinfunction "GND_1") (pintype "power_in"))
      (node (ref "U1") (pin "28") (pinfunction "GND_28") (pintype "power_in"))
      (node (ref "U1") (pin "29_1") (pinfunction "GND_29_1") (pintype "power_in"))
      (node (ref "U1") (pin "29_2") (pinfunction "GND_29_2") (pintype "power_in"))
      (node (ref "U1") (pin "29_3") (pinfunction "GND_29_3") (pintype "power_in"))
      (node (ref "U1") (pin "29_4") (pinfunction "GND_29_4") (pintype "power_in"))
      (node (ref "U1") (pin "29_5") (pinfunction "GND_29_5") (pintype "power_in"))
      (node (ref "U1") (pin "29_6") (pinfunction "GND_29_6") (pintype "power_in"))
      (node (ref "U1") (pin "29_7") (pinfunction "GND_29_7") (pintype "power_in"))
      (node (ref "U1") (pin "29_8") (pinfunction "GND_29_8") (pintype "power_in"))
      (node (ref "U1") (pin "29_9") (pinfunction "GND_29_9") (pintype "power_in"))
      (node (ref "U2") (pin "1") (pinfunction "CTG_1") (pintype "power_in"))
      (node (ref "U2") (pin "4") (pinfunction "GND_4") (pintype "power_in"))
      (node (ref "U2") (pin "6") (pinfunction "QSTRT_6") (pintype "input"))
      (node (ref "U2") (pin "9") (pinfunction "EP_9") (pintype "power_in"))
      (node (ref "U3") (pin "4") (pinfunction "GND_4") (pintype "power_in"))
      (node (ref "U3") (pin "9") (pinfunction "EXP_9") (pintype "passive"))
      (node (ref "U4") (pin "2") (pinfunction "VSS_2") (pintype "power_in"))
      (node (ref "U5") (pin "1") (pinfunction "GND_1") (pintype "power_in"))
      (node (ref "U5") (pin "5") (pinfunction "SDO_5") (pintype "bidirectional"))
      (node (ref "U5") (pin "7") (pinfunction "GND_7") (pintype "power_in"))
      (node (ref "U6") (pin "13") (pinfunction "GND_13") (pintype "power_in"))
    )
    (net (code "14") (name "GPIO8") (class "Default")
      (node (ref "R6") (pin "1") (pinfunction "1_1") (pintype "passive"))
      (node (ref "U1") (pin "10") (pinfunction "IO8_10") (pintype "bidirectional"))
    )
    (net (code "15") (name "I2C_PW") (class "Default")
      (node (ref "C21") (pin "1") (pinfunction "1_1") (pintype "passive"))
      (node (ref "C22") (pin "1") (pinfunction "1_1") (pintype "passive"))
      (node (ref "R12") (pin "2") (pinfunction "2_2") (pintype "passive"))
      (node (ref "R13") (pin "2") (pinfunction "2_2") (pintype "passive"))
      (node (ref "U1") (pin "17") (pinfunction "IO19_17") (pintype "bidirectional"))
      (node (ref "U5") (pin "2") (pinfunction "CSB_2") (pintype "input"))
      (node (ref "U5") (pin "6") (pinfunction "VDDIO_6") (pintype "power_in"))
      (node (ref "U5") (pin "8") (pinfunction "VDD_8") (pintype "power_in"))
    )
    (net (code "16") (name "INT_RTC") (class "Default")
      (node (ref "R16") (pin "1") (pinfunction "1_1") (pintype "passive"))
      (node (ref "TP15") (pin "TP") (pinfunction "TP_TP") (pintype "input"))
      (node (ref "U1") (pin "8") (pinfunction "IO0_8") (pintype "bidirectional"))
      (node (ref "U6") (pin "3") (pinfunction "SQW/~{INT}_3") (pintype "output"))
    )
    (net (code "17") (name "IO{slash}BOOT") (class "Default")
      (node (ref "C27") (pin "1") (pinfunction "1_1") (pintype "passive"))
      (node (ref "R18") (pin "1") (pinfunction "1_1") (pintype "passive"))
      (node (ref "U$2") (pin "3") (pinfunction "3_3") (pintype "passive"))
      (node (ref "U$2") (pin "4") (pinfunction "4_4") (pintype "passive"))
      (node (ref "U1") (pin "15") (pinfunction "IO9_15") (pintype "bidirectional"))
    )
    (net (code "18") (name "IO{slash}CHANGE") (class "Default")
      (node (ref "C28") (pin "1") (pinfunction "1_1") (pintype "passive"))
      (node (ref "R19") (pin "1") (pinfunction "1_1") (pintype "passive"))
      (node (ref "U$3") (pin "3") (pinfunction "3_3") (pintype "passive"))
      (node (ref "U$3") (pin "4") (pinfunction "4_4") (pintype "passive"))
      (node (ref "U1") (pin "23") (pinfunction "IO15_23") (pintype "bidirectional"))
    )
    (net (code "19") (name "MISO") (class "Default")
      (node (ref "D7") (pin "2") (pinfunction "2_2") (pintype "passive"))
      (node (ref "J2") (pin "P7") (pinfunction "DAT0_P7") (pintype "bidirectional"))
      (node (ref "R31") (pin "1") (pinfunction "1_1") (pintype "passive"))
      (node (ref "TP6") (pin "TP") (pinfunction "TP_TP") (pintype "input"))
      (node (ref "U1") (pin "27") (pinfunction "IO2_27") (pintype "bidirectional"))
      (node (ref "U3") (pin "2") (pinfunction "DO(IO1)_2") (pintype "bidirectional"))
    )
    (net (code "20") (name "MOSI") (class "Default")
      (node (ref "D8") (pin "2") (pinfunction "2_2") (pintype "passive"))
      (node (ref "J2") (pin "P3") (pinfunction "CMD_P3") (pintype "bidirectional"))
      (node (ref "J4") (pin "14") (pinfunction "14_14") (pintype "bidirectional"))
      (node (ref "R30") (pin "1") (pinfunction "1_1") (pintype "passive"))
      (node (ref "TP7") (pin "TP") (pinfunction "TP_TP") (pintype "input"))
      (node (ref "U1") (pin "7") (pinfunction "IO7_7") (pintype "bidirectional"))
      (node (ref "U3") (pin "5") (pinfunction "DI(IO0)_5") (pintype "bidirectional"))
    )
    (net (code "21") (name "Net-(C11-Pad2)") (class "Default")
      (node (ref "C11") (pin "2") (pinfunction "2_2") (pintype "passive"))
      (node (ref "J4") (pin "4") (pinfunction "4_4") (pintype "bidirectional"))
    )
    (net (code "22") (name "Net-(C12-Pad2)") (class "Default")
      (node (ref "C12") (pin "2") (pinfunction "2_2") (pintype "passive"))
      (node (ref "J4") (pin "5") (pinfunction "5_5") (pintype "bidirectional"))
    )
    (net (code "23") (name "Net-(C14-Pad2)") (class "Default")
      (node (ref "C14") (pin "2") (pinfunction "2_2") (pintype "passive"))
      (node (ref "J4") (pin "22") (pinfunction "22_22") (pintype "bidirectional"))
    )
    (net (code "24") (name "Net-(C17-Pad2)") (class "Default")
      (node (ref "C17") (pin "2") (pinfunction "2_2") (pintype "passive"))
      (node (ref "J4") (pin "24") (pinfunction "24_24") (pintype "bidirectional"))
    )
    (net (code "25") (name "Net-(C18-Pad2)") (class "Default")
      (node (ref "C18") (pin "2") (pinfunction "2_2") (pintype "passive"))
      (node (ref "J4") (pin "20") (pinfunction "20_20") (pintype "bidirectional"))
    )
    (net (code "26") (name "Net-(C19-Pad2)") (class "Default")
      (node (ref "C19") (pin "2") (pinfunction "2_2") (pintype "passive"))
      (node (ref "J4") (pin "19") (pinfunction "19_19") (pintype "bidirectional"))
    )
    (net (code "27") (name "Net-(C20-Pad2)") (class "Default")
      (node (ref "C20") (pin "2") (pinfunction "2_2") (pintype "passive"))
      (node (ref "J4") (pin "18") (pinfunction "18_18") (pintype "bidirectional"))
    )
    (net (code "28") (name "Net-(D2-CATHODE)") (class "Default")
      (node (ref "C5") (pin "1") (pinfunction "1_1") (pintype "passive"))
      (node (ref "D2") (pin "1") (pinfunction "CATHODE_1") (pintype "bidirectional"))
      (node (ref "IC1") (pin "1") (pinfunction "VIN_1") (pintype "bidirectional"))
      (node (ref "IC1") (pin "3") (pinfunction "CE_3") (pintype "bidirectional"))
      (node (ref "Q1") (pin "2") (pinfunction "S_2") (pintype "bidirectional"))
    )
    (net (code "29") (name "Net-(D3-K)") (class "Default")
      (node (ref "C7") (pin "1") (pinfunction "1_1") (pintype "passive"))
      (node (ref "D3") (pin "1") (pinfunction "K_1") (pintype "bidirectional"))
      (node (ref "D4") (pin "2") (pinfunction "A_2") (pintype "bidirectional"))
    )
    (net (code "30") (name "Net-(D6-CATHODE)") (class "Default")
      (node (ref "D6") (pin "1") (pinfunction "CATHODE_1") (pintype "bidirectional"))
      (node (ref "R14") (pin "1") (pinfunction "1_1") (pintype "passive"))
    )
    (net (code "31") (name "Net-(IC2-CT)") (class "Default")
      (node (ref "C25") (pin "1") (pinfunction "1_1") (pintype "passive"))
      (node (ref "IC2") (pin "5") (pinfunction "CT_5") (pintype "bidirectional"))
    )
    (net (code "32") (name "Net-(J1-PadA5)") (class "Default")
      (node (ref "J1") (pin "A5") (pinfunction "A5_A5") (pintype "bidirectional"))
      (node (ref "R3") (pin "2") (pinfunction "2_2") (pintype "passive"))
    )
    (net (code "33") (name "Net-(J1-PadB5)") (class "Default")
      (node (ref "J1") (pin "B5") (pinfunction "B5_B5") (pintype "bidirectional"))
      (node (ref "R1") (pin "1") (pinfunction "1_1") (pintype "passive"))
    )
    (net (code "34") (name "Net-(LED1-PadC)") (class "Default")
      (node (ref "LED1") (pin "C") (pinfunction "C_C") (pintype "passive"))
      (node (ref "R10") (pin "1") (pinfunction "1_1") (pintype "passive"))
    )
    (net (code "35") (name "Net-(U4-PROG)") (class "Default")
      (node (ref "R11") (pin "2") (pinfunction "2_2") (pintype "passive"))
      (node (ref "U4") (pin "5") (pinfunction "PROG_5") (pintype "input"))
    )
    (net (code "36") (name "Net-(U4-STAT)") (class "Default")
      (node (ref "R10") (pin "2") (pinfunction "2_2") (pintype "passive"))
      (node (ref "U4") (pin "1") (pinfunction "STAT_1") (pintype "output"))
    )
    (net (code "37") (name "PREVGH") (class "Default")
      (node (ref "C16") (pin "2") (pinfunction "2_2") (pintype "passive"))
      (node (ref "D5") (pin "1") (pinfunction "K_1") (pintype "bidirectional"))
      (node (ref "J4") (pin "21") (pinfunction "21_21") (pintype "bidirectional"))
    )
    (net (code "38") (name "PREVGL") (class "Default")
      (node (ref "C15") (pin "2") (pinfunction "2_2") (pintype "passive"))
      (node (ref "D3") (pin "2") (pinfunction "A_2") (pintype "bidirectional"))
      (node (ref "J4") (pin "23") (pinfunction "23_23") (pintype "bidirectional"))
    )
    (net (code "39") (name "RESE") (class "Default")
      (node (ref "J4") (pin "3") (pinfunction "3_3") (pintype "bidirectional"))
      (node (ref "Q3") (pin "2") (pinfunction "S_2") (pintype "bidirectional"))
      (node (ref "R9") (pin "2") (pinfunction "2_2") (pintype "passive"))
    )
    (net (code "40") (name "RESE'") (class "Default")
      (node (ref "R5") (pin "2") (pinfunction "2_2") (pintype "passive"))
      (node (ref "R9") (pin "1") (pinfunction "1_1") (pintype "passive"))
      (node (ref "SJ1") (pin "2") (pinfunction "2_2") (pintype "passive"))
    )
    (net (code "41") (name "RESET") (class "Default")
      (node (ref "C26") (pin "1") (pinfunction "1_1") (pintype "passive"))
      (node (ref "IC2") (pin "1") (pinfunction "VOUT_1") (pintype "bidirectional"))
      (node (ref "R17") (pin "1") (pinfunction "1_1") (pintype "passive"))
      (node (ref "U$1") (pin "3") (pinfunction "3_3") (pintype "passive"))
      (node (ref "U$1") (pin "4") (pinfunction "4_4") (pintype "passive"))
      (node (ref "U1") (pin "3") (pinfunction "EN_3") (pintype "input"))
    )
    (net (code "42") (name "RTC_RST") (class "Default")
      (node (ref "U1") (pin "16") (pinfunction "IO18_16") (pintype "bidirectional"))
      (node (ref "U6") (pin "4") (pinfunction "~{RST}_4") (pintype "input"))
    )
    (net (code "43") (name "RX") (class "Default")
      (node (ref "TP2") (pin "TP") (pinfunction "TP_TP") (pintype "input"))
      (node (ref "U1") (pin "24") (pinfunction "RXD0/GPIO17_24") (pintype "bidirectional"))
    )
    (net (code "44") (name "SCK") (class "Default")
      (node (ref "D9") (pin "2") (pinfunction "2_2") (pintype "passive"))
      (node (ref "J2") (pin "P5") (pinfunction "CLK_P5") (pintype "bidirectional"))
      (node (ref "J4") (pin "13") (pinfunction "13_13") (pintype "bidirectional"))
      (node (ref "R29") (pin "1") (pinfunction "1_1") (pintype "passive"))
      (node (ref "TP8") (pin "TP") (pinfunction "TP_TP") (pintype "input"))
      (node (ref "U1") (pin "6") (pinfunction "IO6_6") (pintype "bidirectional"))
      (node (ref "U3") (pin "6") (pinfunction "CLK_6") (pintype "input"))
    )
    (net (code "45") (name "SCL") (class "Default")
      (node (ref "J3") (pin "4") (pinfunction "4_4") (pintype "passive"))
      (node (ref "R12") (pin "1") (pinfunction "1_1") (pintype "passive"))
      (node (ref "U1") (pin "20") (pinfunction "IO22_20") (pintype "bidirectional"))
      (node (ref "U2") (pin "7") (pinfunction "SCL_7") (pintype "input"))
      (node (ref "U5") (pin "4") (pinfunction "SCK_4") (pintype "input"))
      (node (ref "U6") (pin "16") (pinfunction "SCL_16") (pintype "input"))
    )
    (net (code "46") (name "SDA") (class "Default")
      (node (ref "J3") (pin "3") (pinfunction "3_3") (pintype "passive"))
      (node (ref "R13") (pin "1") (pinfunction "1_1") (pintype "passive"))
      (node (ref "U1") (pin "19") (pinfunction "IO21_19") (pintype "bidirectional"))
      (node (ref "U2") (pin "8") (pinfunction "SDA_8") (pintype "bidirectional"))
      (node (ref "U5") (pin "3") (pinfunction "SDI_3") (pintype "bidirectional"))
      (node (ref "U6") (pin "15") (pinfunction "SDA_15") (pintype "bidirectional"))
    )
    (net (code "47") (name "SRC") (class "Default")
      (node (ref "C7") (pin "2") (pinfunction "2_2") (pintype "passive"))
      (node (ref "D5") (pin "2") (pinfunction "A_2") (pintype "bidirectional"))
      (node (ref "L1") (pin "1") (pinfunction "1_1") (pintype "passive"))
      (node (ref "Q3") (pin "3") (pinfunction "D_3") (pintype "bidirectional"))
    )
    (net (code "48") (name "SS_SD") (class "Default")
      (node (ref "D12") (pin "2") (pinfunction "2_2") (pintype "passive"))
      (node (ref "J2") (pin "P2") (pinfunction "CD/DAT3_P2") (pintype "bidirectional"))
      (node (ref "R26") (pin "1") (pinfunction "1_1") (pintype "passive"))
      (node (ref "U1") (pin "4") (pinfunction "IO4_4") (pintype "bidirectional"))
    )
    (net (code "49") (name "TX") (class "Default")
      (node (ref "TP1") (pin "TP") (pinfunction "TP_TP") (pintype "input"))
      (node (ref "U1") (pin "25") (pinfunction "TXD0/GPIO16_25") (pintype "bidirectional"))
    )
    (net (code "50") (name "USB_D+") (class "Default")
      (node (ref "D1") (pin "1") (pinfunction "I/O1_1_1") (pintype "bidirectional"))
      (node (ref "U1") (pin "14") (pinfunction "IO13_14") (pintype "bidirectional"))
    )
    (net (code "51") (name "USB_D-") (class "Default")
      (node (ref "D1") (pin "3") (pinfunction "I/O2_1_3") (pintype "bidirectional"))
      (node (ref "U1") (pin "13") (pinfunction "IO12_13") (pintype "bidirectional"))
    )
    (net (code "52") (name "VBAT") (class "Default")
      (node (ref "C10") (pin "1") (pinfunction "1_1") (pintype "passive"))
      (node (ref "Q1") (pin "3") (pinfunction "D_3") (pintype "bidirectional"))
      (node (ref "TP3") (pin "TP") (pinfunction "TP_TP") (pintype "input"))
      (node (ref "U2") (pin "2") (pinfunction "CELL_2") (pintype "power_in"))
      (node (ref "U2") (pin "3") (pinfunction "VDD_3") (pintype "power_in"))
      (node (ref "U4") (pin "3") (pinfunction "VBAT_3") (pintype "power_in"))
    )
    (net (code "53") (name "VBUS") (class "Default")
      (node (ref "C1") (pin "1") (pinfunction "1_1") (pintype "passive"))
      (node (ref "C2") (pin "1") (pinfunction "1_1") (pintype "passive"))
      (node (ref "C9") (pin "1") (pinfunction "1_1") (pintype "passive"))
      (node (ref "D1") (pin "5") (pinfunction "VBUS_5") (pintype "bidirectional"))
      (node (ref "D2") (pin "2") (pinfunction "ANODE_2") (pintype "bidirectional"))
      (node (ref "LED1") (pin "A") (pinfunction "A_A") (pintype "passive"))
      (node (ref "Q1") (pin "1") (pinfunction "G_1") (pintype "bidirectional"))
      (node (ref "R2") (pin "2") (pinfunction "2_2") (pintype "passive"))
      (node (ref "R4") (pin "2") (pinfunction "2_2") (pintype "passive"))
      (node (ref "TP14") (pin "TP") (pinfunction "TP_TP") (pintype "input"))
      (node (ref "U4") (pin "4") (pinfunction "VIN_4") (pintype "power_in"))
    )
    (net (code "54") (name "VRTC") (class "Default")
      (node (ref "C23") (pin "1") (pinfunction "1_1") (pintype "passive"))
      (node (ref "C24") (pin "1") (pinfunction "1_1") (pintype "passive"))
      (node (ref "R14") (pin "2") (pinfunction "2_2") (pintype "passive"))
      (node (ref "U6") (pin "14") (pinfunction "VBAT_14") (pintype "power_in"))
    )
    (net (code "55") (name "VUSB") (class "Default")
      (node (ref "J1") (pin "A4") (pinfunction "A4_A4") (pintype "bidirectional"))
      (node (ref "J1") (pin "A9") (pinfunction "A9_A9") (pintype "bidirectional"))
      (node (ref "J1") (pin "B4") (pinfunction "B4_B4") (pintype "bidirectional"))
      (node (ref "J1") (pin "B9") (pinfunction "B9_B9") (pintype "bidirectional"))
      (node (ref "R2") (pin "1") (pinfunction "1_1") (pintype "passive"))
    )
    (net (code "56") (name "unconnected-(IC1-NC-Pad4)") (class "Default")
      (node (ref "IC1") (pin "4") (pinfunction "NC_4") (pintype "no_connect"))
    )
    (net (code "57") (name "unconnected-(IC2-NC-Pad4)") (class "Default")
      (node (ref "IC2") (pin "4") (pinfunction "NC_4") (pintype "no_connect"))
    )
    (net (code "58") (name "unconnected-(J1-PadA8)") (class "Default")
      (node (ref "J1") (pin "A8") (pinfunction "A8_A8") (pintype "bidirectional"))
    )
    (net (code "59") (name "unconnected-(J1-PadB8)") (class "Default")
      (node (ref "J1") (pin "B8") (pinfunction "B8_B8") (pintype "bidirectional"))
    )
    (net (code "60") (name "unconnected-(J2-DAT1-PadP8)") (class "Default")
      (node (ref "J2") (pin "P8") (pinfunction "DAT1_P8") (pintype "bidirectional"))
    )
    (net (code "61") (name "unconnected-(J2-DAT2-PadP1)") (class "Default")
      (node (ref "J2") (pin "P1") (pinfunction "DAT2_P1") (pintype "bidirectional"))
    )
    (net (code "62") (name "unconnected-(J2-DETECTION_1-PadS1)") (class "Default")
      (node (ref "J2") (pin "S1") (pinfunction "DETECTION_1_S1") (pintype "bidirectional"))
    )
    (net (code "63") (name "unconnected-(J2-DETECTION_2-PadS2)") (class "Default")
      (node (ref "J2") (pin "S2") (pinfunction "DETECTION_2_S2") (pintype "bidirectional"))
    )
    (net (code "64") (name "unconnected-(J4-Pad1)") (class "Default")
      (node (ref "J4") (pin "1") (pinfunction "1_1") (pintype "bidirectional"))
    )
    (net (code "65") (name "unconnected-(J4-Pad6)") (class "Default")
      (node (ref "J4") (pin "6") (pinfunction "6_6") (pintype "bidirectional"))
    )
    (net (code "66") (name "unconnected-(J4-Pad7)") (class "Default")
      (node (ref "J4") (pin "7") (pinfunction "7_7") (pintype "bidirectional"))
    )
    (net (code "67") (name "unconnected-(U1-NC-Pad22)") (class "Default")
      (node (ref "U1") (pin "22") (pinfunction "NC_22") (pintype "no_connect"))
    )
    (net (code "68") (name "unconnected-(U2-~{ALERT}-Pad5)") (class "Default")
      (node (ref "U2") (pin "5") (pinfunction "~{ALERT}_5") (pintype "output"))
    )
  )
)
